# CTRL_LOGIC.net
KiCad netlist of a schematic drawn in Altium Designer
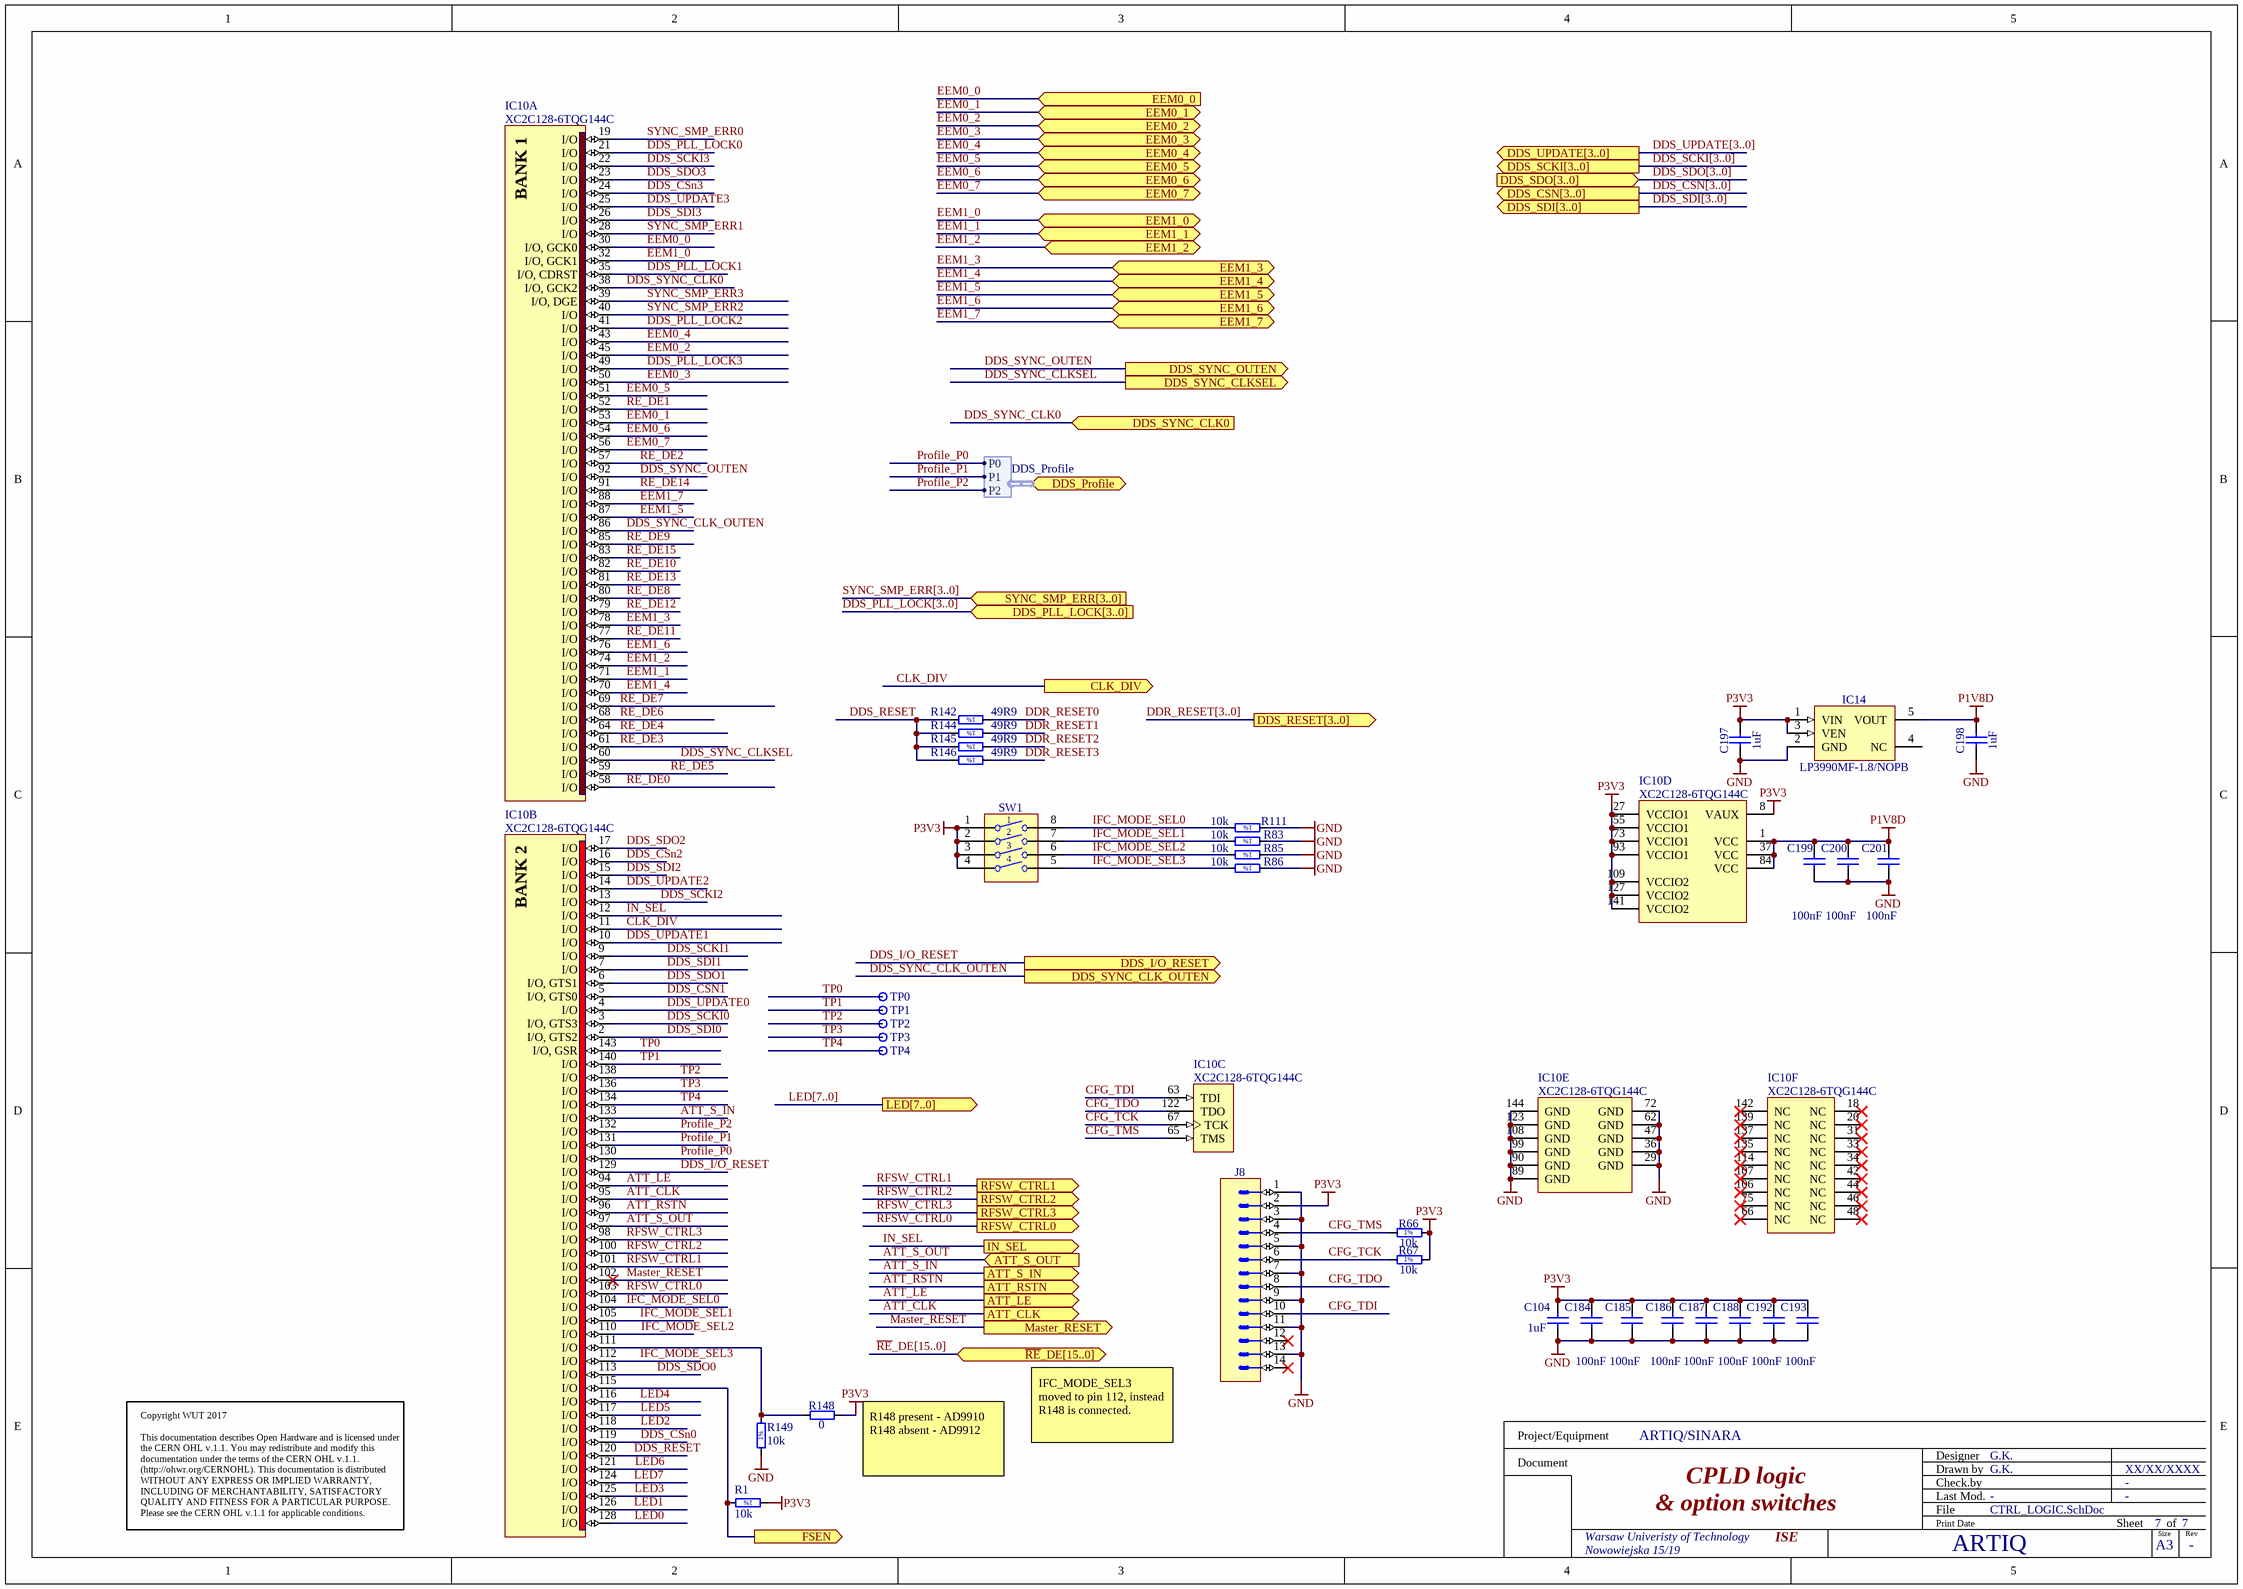
[diagram p0: CTRL_LOGIC.SchDoc]

(export (version "E")
  (design (tool "Eeschema 10.0.6"))
  (components
    (comp (ref "C104")
      (value "1uF")
      (footprint "CAPC1005X55N")
      (description "Non-polarised capacitor")
      (fields
        (field (name "PART NUMBER") "CC0402_1UF_16V_10%_X5R")
        (field (name "VOLTAGE") "16V")
        (field (name "AUTHOR") "CERN DEM JLC")
      )
      (libsource (lib "Capacitors") (part "Capacitor - non polarized"))
    )
    (comp (ref "C184")
      (value "100nF")
      (footprint "CAPC1005X55N")
      (description "Non-polarised capacitor")
      (fields
        (field (name "PART NUMBER") "CC0402_100NF_16V_10%_X5R")
        (field (name "VOLTAGE") "16V")
        (field (name "AUTHOR") "CERN DEM JLC")
      )
      (libsource (lib "Capacitors") (part "Capacitor - non polarized"))
    )
    (comp (ref "C185")
      (value "100nF")
      (footprint "CAPC1005X55N")
      (description "Non-polarised capacitor")
      (fields
        (field (name "PART NUMBER") "CC0402_100NF_16V_10%_X5R")
        (field (name "VOLTAGE") "16V")
        (field (name "AUTHOR") "CERN DEM JLC")
      )
      (libsource (lib "Capacitors") (part "Capacitor - non polarized"))
    )
    (comp (ref "C186")
      (value "100nF")
      (footprint "CAPC1005X55N")
      (description "Non-polarised capacitor")
      (fields
        (field (name "PART NUMBER") "CC0402_100NF_16V_10%_X5R")
        (field (name "VOLTAGE") "16V")
        (field (name "AUTHOR") "CERN DEM JLC")
      )
      (libsource (lib "Capacitors") (part "Capacitor - non polarized"))
    )
    (comp (ref "C187")
      (value "100nF")
      (footprint "CAPC1005X55N")
      (description "Non-polarised capacitor")
      (fields
        (field (name "PART NUMBER") "CC0402_100NF_16V_10%_X5R")
        (field (name "VOLTAGE") "16V")
        (field (name "AUTHOR") "CERN DEM JLC")
      )
      (libsource (lib "Capacitors") (part "Capacitor - non polarized"))
    )
    (comp (ref "C188")
      (value "100nF")
      (footprint "CAPC1005X55N")
      (description "Non-polarised capacitor")
      (fields
        (field (name "PART NUMBER") "CC0402_100NF_16V_10%_X5R")
        (field (name "VOLTAGE") "16V")
        (field (name "AUTHOR") "CERN DEM JLC")
      )
      (libsource (lib "Capacitors") (part "Capacitor - non polarized"))
    )
    (comp (ref "C192")
      (value "100nF")
      (footprint "CAPC1005X55N")
      (description "Non-polarised capacitor")
      (fields
        (field (name "PART NUMBER") "CC0402_100NF_16V_10%_X5R")
        (field (name "VOLTAGE") "16V")
        (field (name "AUTHOR") "CERN DEM JLC")
      )
      (libsource (lib "Capacitors") (part "Capacitor - non polarized"))
    )
    (comp (ref "C193")
      (value "100nF")
      (footprint "CAPC1005X55N")
      (description "Non-polarised capacitor")
      (fields
        (field (name "PART NUMBER") "CC0402_100NF_16V_10%_X5R")
        (field (name "VOLTAGE") "16V")
        (field (name "AUTHOR") "CERN DEM JLC")
      )
      (libsource (lib "Capacitors") (part "Capacitor - non polarized"))
    )
    (comp (ref "C197")
      (value "1uF")
      (footprint "CAPC1005X55N")
      (description "Non-polarised capacitor")
      (fields
        (field (name "PART NUMBER") "CC0402_1UF_16V_10%_X5R")
        (field (name "VOLTAGE") "16V")
        (field (name "AUTHOR") "CERN DEM JLC")
      )
      (libsource (lib "Capacitors") (part "Capacitor - non polarized"))
    )
    (comp (ref "C198")
      (value "1uF")
      (footprint "CAPC1005X55N")
      (description "Non-polarised capacitor")
      (fields
        (field (name "PART NUMBER") "CC0402_1UF_16V_10%_X5R")
        (field (name "VOLTAGE") "16V")
        (field (name "AUTHOR") "CERN DEM JLC")
      )
      (libsource (lib "Capacitors") (part "Capacitor - non polarized"))
    )
    (comp (ref "C199")
      (value "100nF")
      (footprint "CAPC1005X55N")
      (description "Non-polarised capacitor")
      (fields
        (field (name "PART NUMBER") "CC0402_100NF_16V_10%_X5R")
        (field (name "VOLTAGE") "16V")
        (field (name "AUTHOR") "CERN DEM JLC")
      )
      (libsource (lib "Capacitors") (part "Capacitor - non polarized"))
    )
    (comp (ref "C200")
      (value "100nF")
      (footprint "CAPC1005X55N")
      (description "Non-polarised capacitor")
      (fields
        (field (name "PART NUMBER") "CC0402_100NF_16V_10%_X5R")
        (field (name "VOLTAGE") "16V")
        (field (name "AUTHOR") "CERN DEM JLC")
      )
      (libsource (lib "Capacitors") (part "Capacitor - non polarized"))
    )
    (comp (ref "C201")
      (value "100nF")
      (footprint "CAPC1005X55N")
      (description "Non-polarised capacitor")
      (fields
        (field (name "PART NUMBER") "CC0402_100NF_16V_10%_X5R")
        (field (name "VOLTAGE") "16V")
        (field (name "AUTHOR") "CERN DEM JLC")
      )
      (libsource (lib "Capacitors") (part "Capacitor - non polarized"))
    )
    (comp (ref "IC10")
      (value "XC2C128-6TQG144C")
      (footprint "QFP50P2200X2200X160-144N")
      (description "CoolRunner-II 1.8V, 128 Macrocell CPLD, 100 User I/Os, 144-Pin TQFP, Commercial Grade, Pb-Free")
      (fields (field (name "MANUFACTURER") "XILINX") (field (name "AUTHOR") "CERN DEM JLC"))
      (libsource (lib "ICs And Semiconductors") (part "XC2C128-6TQG144C"))
    )
    (comp (ref "IC14")
      (value "LP3990MF-1.8/NOPB")
      (footprint "SOT95P284X122-5N")
      (description "1.8V, 150mA Linear Voltage Regulator For Digital Applications")
      (fields (field (name "MANUFACTURER") "TEXAS INSTRUMENTS") (field (name "AUTHOR") "CERN DEM JLC"))
      (libsource (lib "ICs And Semiconductors") (part "LP3990MF"))
    )
    (comp (ref "J8")
      (value "Milli-Grid™")
      (footprint "MOLEX_87832-1420")
      (description "Connector 14 Male")
      (fields
        (field (name "PART NUMBER") "MOLEX_87832-1420")
        (field (name "MANUFACTURER") "MOLEX")
        (field (name "AUTHOR") "CERN DEM JLC")
      )
      (libsource (lib "Connectors") (part "Connector 14 Male"))
    )
    (comp (ref "R1")
      (value "10k")
      (footprint "RESC1005X40N")
      (description "Resistor - 1%")
      (fields
        (field (name "PART NUMBER") "R0402_10K_1%_0.0625W_100PPM")
        (field (name "POWER") "0.0625W")
        (field (name "AUTHOR") "CERN DEM JLC")
      )
      (libsource (lib "Resistors") (part "Resistor - 1%"))
    )
    (comp (ref "R66")
      (value "10k")
      (footprint "RESC1005X40N")
      (description "Resistor - 1%")
      (fields
        (field (name "PART NUMBER") "R0402_10K_1%_0.0625W_100PPM")
        (field (name "POWER") "0.0625W")
        (field (name "AUTHOR") "CERN DEM JLC")
      )
      (libsource (lib "Resistors") (part "Resistor - 1%"))
    )
    (comp (ref "R67")
      (value "10k")
      (footprint "RESC1005X40N")
      (description "Resistor - 1%")
      (fields
        (field (name "PART NUMBER") "R0402_10K_1%_0.0625W_100PPM")
        (field (name "POWER") "0.0625W")
        (field (name "AUTHOR") "CERN DEM JLC")
      )
      (libsource (lib "Resistors") (part "Resistor - 1%"))
    )
    (comp (ref "R83")
      (value "10k")
      (footprint "RESC1005X40N")
      (description "Resistor - 1%")
      (fields
        (field (name "PART NUMBER") "R0402_10K_1%_0.0625W_100PPM")
        (field (name "POWER") "0.0625W")
        (field (name "AUTHOR") "CERN DEM JLC")
      )
      (libsource (lib "Resistors") (part "Resistor - 1%"))
    )
    (comp (ref "R85")
      (value "10k")
      (footprint "RESC1005X40N")
      (description "Resistor - 1%")
      (fields
        (field (name "PART NUMBER") "R0402_10K_1%_0.0625W_100PPM")
        (field (name "POWER") "0.0625W")
        (field (name "AUTHOR") "CERN DEM JLC")
      )
      (libsource (lib "Resistors") (part "Resistor - 1%"))
    )
    (comp (ref "R86")
      (value "10k")
      (footprint "RESC1005X40N")
      (description "Resistor - 1%")
      (fields
        (field (name "PART NUMBER") "R0402_10K_1%_0.0625W_100PPM")
        (field (name "POWER") "0.0625W")
        (field (name "AUTHOR") "CERN DEM JLC")
      )
      (libsource (lib "Resistors") (part "Resistor - 1%"))
    )
    (comp (ref "R111")
      (value "10k")
      (footprint "RESC1005X40N")
      (description "Resistor - 1%")
      (fields
        (field (name "PART NUMBER") "R0402_10K_1%_0.0625W_100PPM")
        (field (name "POWER") "0.0625W")
        (field (name "AUTHOR") "CERN DEM JLC")
      )
      (libsource (lib "Resistors") (part "Resistor - 1%"))
    )
    (comp (ref "R142")
      (value "49R9")
      (footprint "RESC1005X40N")
      (description "Resistor - 1%")
      (fields
        (field (name "PART NUMBER") "R0402_49R9_1%_0.0625W_100PPM")
        (field (name "POWER") "0.0625W")
        (field (name "AUTHOR") "CERN DEM JLC")
      )
      (libsource (lib "Resistors") (part "Resistor - 1%"))
    )
    (comp (ref "R144")
      (value "49R9")
      (footprint "RESC1005X40N")
      (description "Resistor - 1%")
      (fields
        (field (name "PART NUMBER") "R0402_49R9_1%_0.0625W_100PPM")
        (field (name "POWER") "0.0625W")
        (field (name "AUTHOR") "CERN DEM JLC")
      )
      (libsource (lib "Resistors") (part "Resistor - 1%"))
    )
    (comp (ref "R145")
      (value "49R9")
      (footprint "RESC1005X40N")
      (description "Resistor - 1%")
      (fields
        (field (name "PART NUMBER") "R0402_49R9_1%_0.0625W_100PPM")
        (field (name "POWER") "0.0625W")
        (field (name "AUTHOR") "CERN DEM JLC")
      )
      (libsource (lib "Resistors") (part "Resistor - 1%"))
    )
    (comp (ref "R146")
      (value "49R9")
      (footprint "RESC1005X40N")
      (description "Resistor - 1%")
      (fields
        (field (name "PART NUMBER") "R0402_49R9_1%_0.0625W_100PPM")
        (field (name "POWER") "0.0625W")
        (field (name "AUTHOR") "CERN DEM JLC")
      )
      (libsource (lib "Resistors") (part "Resistor - 1%"))
    )
    (comp (ref "R148")
      (value "0")
      (footprint "RESC1005X40N")
      (description "Resistor")
      (fields
        (field (name "PART NUMBER") "R0402_0R_JUMPER")
        (field (name "MANUFACTURER") "GENERIC")
        (field (name "AUTHOR") "CERN DEM JLC")
      )
      (libsource (lib "Resistors") (part "Resistor"))
    )
    (comp (ref "R149")
      (value "10k")
      (footprint "RESC1005X40N")
      (description "Resistor - 1%")
      (fields
        (field (name "PART NUMBER") "R0402_10K_1%_0.0625W_100PPM")
        (field (name "POWER") "0.0625W")
        (field (name "AUTHOR") "CERN DEM JLC")
      )
      (libsource (lib "Resistors") (part "Resistor - 1%"))
    )
    (comp (ref "SW1")
      (value "Switch")
      (footprint "SW_OMRON_A6S-4102-H")
      (description "4 Ways SPST DIP Switch")
      (fields
        (field (name "PART NUMBER") "SW_OMRON_A6S-4102-H")
        (field (name "MANUFACTURER") "OMRON")
        (field (name "AUTHOR") "CERN DEM JMW")
      )
      (libsource (lib "Eletro-mechanical") (part "SW 4x SPST DIP Switch"))
    )
    (comp (ref "TP0")
      (value "Test Point")
      (footprint "TPS127")
      (fields (field (name "PART NUMBER") "SMD_PAD_1.27X1.27MM") (field (name "AUTHOR") "CERN DEM JLC"))
      (libsource (lib "Eletro-mechanical") (part "Test Point"))
    )
    (comp (ref "TP1")
      (value "Test Point")
      (footprint "TPS127")
      (fields (field (name "PART NUMBER") "SMD_PAD_1.27X1.27MM") (field (name "AUTHOR") "CERN DEM JLC"))
      (libsource (lib "Eletro-mechanical") (part "Test Point"))
    )
    (comp (ref "TP2")
      (value "Test Point")
      (footprint "TPS127")
      (fields (field (name "PART NUMBER") "SMD_PAD_1.27X1.27MM") (field (name "AUTHOR") "CERN DEM JLC"))
      (libsource (lib "Eletro-mechanical") (part "Test Point"))
    )
    (comp (ref "TP3")
      (value "Test Point")
      (footprint "TPS127")
      (fields (field (name "PART NUMBER") "SMD_PAD_1.27X1.27MM") (field (name "AUTHOR") "CERN DEM JLC"))
      (libsource (lib "Eletro-mechanical") (part "Test Point"))
    )
    (comp (ref "TP4")
      (value "Test Point")
      (footprint "TPS127")
      (fields (field (name "PART NUMBER") "SMD_PAD_1.27X1.27MM") (field (name "AUTHOR") "CERN DEM JLC"))
      (libsource (lib "Eletro-mechanical") (part "Test Point"))
    )
  )
  (nets
    (net (code "5") (name "/ATT_CLK") (class "Default")
      (node (ref "IC10") (pin "95") (pinfunction "I/O_95") (pintype "bidirectional"))
    )
    (net (code "6") (name "/ATT_LE") (class "Default")
      (node (ref "IC10") (pin "94") (pinfunction "I/O_94") (pintype "bidirectional"))
    )
    (net (code "7") (name "/ATT_RSTN") (class "Default")
      (node (ref "IC10") (pin "96") (pinfunction "I/O_96") (pintype "bidirectional"))
    )
    (net (code "8") (name "/ATT_S_IN") (class "Default")
      (node (ref "IC10") (pin "133") (pinfunction "I/O_133") (pintype "bidirectional"))
    )
    (net (code "9") (name "/ATT_S_OUT") (class "Default")
      (node (ref "IC10") (pin "97") (pinfunction "I/O_97") (pintype "bidirectional"))
    )
    (net (code "10") (name "/CFG_TCK") (class "Default")
      (node (ref "IC10") (pin "67") (pinfunction "TCK_67") (pintype "input"))
      (node (ref "J8") (pin "6") (pinfunction "6_6") (pintype "bidirectional"))
      (node (ref "R67") (pin "1") (pinfunction "1_1") (pintype "passive"))
    )
    (net (code "11") (name "/CFG_TDI") (class "Default")
      (node (ref "IC10") (pin "63") (pinfunction "TDI_63") (pintype "input"))
      (node (ref "J8") (pin "10") (pinfunction "10_10") (pintype "bidirectional"))
    )
    (net (code "12") (name "/CFG_TDO") (class "Default")
      (node (ref "IC10") (pin "122") (pinfunction "TDO_122") (pintype "passive"))
      (node (ref "J8") (pin "8") (pinfunction "8_8") (pintype "bidirectional"))
    )
    (net (code "13") (name "/CFG_TMS") (class "Default")
      (node (ref "IC10") (pin "65") (pinfunction "TMS_65") (pintype "input"))
      (node (ref "J8") (pin "4") (pinfunction "4_4") (pintype "bidirectional"))
      (node (ref "R66") (pin "1") (pinfunction "1_1") (pintype "passive"))
    )
    (net (code "14") (name "/CLK_DIV") (class "Default")
      (node (ref "IC10") (pin "11") (pinfunction "I/O_11") (pintype "bidirectional"))
    )
    (net (code "15") (name "/DDR_RESET0") (class "Default")
      (node (ref "R142") (pin "1") (pinfunction "1_1") (pintype "passive"))
    )
    (net (code "16") (name "/DDR_RESET1") (class "Default")
      (node (ref "R144") (pin "1") (pinfunction "1_1") (pintype "passive"))
    )
    (net (code "17") (name "/DDR_RESET2") (class "Default")
      (node (ref "R145") (pin "1") (pinfunction "1_1") (pintype "passive"))
    )
    (net (code "18") (name "/DDR_RESET3") (class "Default")
      (node (ref "R146") (pin "1") (pinfunction "1_1") (pintype "passive"))
    )
    (net (code "20") (name "/DDS_CSN1") (class "Default")
      (node (ref "IC10") (pin "5") (pinfunction "I/O,_GTS0_5") (pintype "bidirectional"))
    )
    (net (code "22") (name "/DDS_CSn0") (class "Default")
      (node (ref "IC10") (pin "119") (pinfunction "I/O_119") (pintype "bidirectional"))
    )
    (net (code "23") (name "/DDS_CSn2") (class "Default")
      (node (ref "IC10") (pin "16") (pinfunction "I/O_16") (pintype "bidirectional"))
    )
    (net (code "24") (name "/DDS_CSn3") (class "Default")
      (node (ref "IC10") (pin "24") (pinfunction "I/O_24") (pintype "bidirectional"))
    )
    (net (code "25") (name "/DDS_I{slash}O_RESET") (class "Default")
      (node (ref "IC10") (pin "129") (pinfunction "I/O_129") (pintype "bidirectional"))
    )
    (net (code "26") (name "/DDS_PLL_LOCK0") (class "Default")
      (node (ref "IC10") (pin "21") (pinfunction "I/O_21") (pintype "bidirectional"))
    )
    (net (code "27") (name "/DDS_PLL_LOCK1") (class "Default")
      (node (ref "IC10") (pin "35") (pinfunction "I/O,_CDRST_35") (pintype "bidirectional"))
    )
    (net (code "28") (name "/DDS_PLL_LOCK2") (class "Default")
      (node (ref "IC10") (pin "41") (pinfunction "I/O_41") (pintype "bidirectional"))
    )
    (net (code "29") (name "/DDS_PLL_LOCK3") (class "Default")
      (node (ref "IC10") (pin "49") (pinfunction "I/O_49") (pintype "bidirectional"))
    )
    (net (code "31") (name "/DDS_RESET") (class "Default")
      (node (ref "IC10") (pin "120") (pinfunction "I/O_120") (pintype "bidirectional"))
      (node (ref "R142") (pin "2") (pinfunction "2_2") (pintype "passive"))
      (node (ref "R144") (pin "2") (pinfunction "2_2") (pintype "passive"))
      (node (ref "R145") (pin "2") (pinfunction "2_2") (pintype "passive"))
      (node (ref "R146") (pin "2") (pinfunction "2_2") (pintype "passive"))
    )
    (net (code "32") (name "/DDS_SCKI0") (class "Default")
      (node (ref "IC10") (pin "3") (pinfunction "I/O,_GTS3_3") (pintype "bidirectional"))
    )
    (net (code "33") (name "/DDS_SCKI1") (class "Default")
      (node (ref "IC10") (pin "9") (pinfunction "I/O_9") (pintype "bidirectional"))
    )
    (net (code "34") (name "/DDS_SCKI2") (class "Default")
      (node (ref "IC10") (pin "13") (pinfunction "I/O_13") (pintype "bidirectional"))
    )
    (net (code "35") (name "/DDS_SCKI3") (class "Default")
      (node (ref "IC10") (pin "22") (pinfunction "I/O_22") (pintype "bidirectional"))
    )
    (net (code "37") (name "/DDS_SDI0") (class "Default")
      (node (ref "IC10") (pin "2") (pinfunction "I/O,_GTS2_2") (pintype "bidirectional"))
    )
    (net (code "38") (name "/DDS_SDI1") (class "Default")
      (node (ref "IC10") (pin "7") (pinfunction "I/O_7") (pintype "bidirectional"))
    )
    (net (code "39") (name "/DDS_SDI2") (class "Default")
      (node (ref "IC10") (pin "15") (pinfunction "I/O_15") (pintype "bidirectional"))
    )
    (net (code "40") (name "/DDS_SDI3") (class "Default")
      (node (ref "IC10") (pin "26") (pinfunction "I/O_26") (pintype "bidirectional"))
    )
    (net (code "42") (name "/DDS_SDO0") (class "Default")
      (node (ref "IC10") (pin "113") (pinfunction "I/O_113") (pintype "bidirectional"))
    )
    (net (code "43") (name "/DDS_SDO1") (class "Default")
      (node (ref "IC10") (pin "6") (pinfunction "I/O,_GTS1_6") (pintype "bidirectional"))
    )
    (net (code "44") (name "/DDS_SDO2") (class "Default")
      (node (ref "IC10") (pin "17") (pinfunction "I/O_17") (pintype "bidirectional"))
    )
    (net (code "45") (name "/DDS_SDO3") (class "Default")
      (node (ref "IC10") (pin "23") (pinfunction "I/O_23") (pintype "bidirectional"))
    )
    (net (code "47") (name "/DDS_SYNC_CLK0") (class "Default")
      (node (ref "IC10") (pin "38") (pinfunction "I/O,_GCK2_38") (pintype "bidirectional"))
    )
    (net (code "48") (name "/DDS_SYNC_CLKSEL") (class "Default")
      (node (ref "IC10") (pin "60") (pinfunction "I/O_60") (pintype "bidirectional"))
    )
    (net (code "49") (name "/DDS_SYNC_CLK_OUTEN") (class "Default")
      (node (ref "IC10") (pin "86") (pinfunction "I/O_86") (pintype "bidirectional"))
    )
    (net (code "50") (name "/DDS_SYNC_OUTEN") (class "Default")
      (node (ref "IC10") (pin "92") (pinfunction "I/O_92") (pintype "bidirectional"))
    )
    (net (code "51") (name "/DDS_UPDATE0") (class "Default")
      (node (ref "IC10") (pin "4") (pinfunction "I/O_4") (pintype "bidirectional"))
    )
    (net (code "52") (name "/DDS_UPDATE1") (class "Default")
      (node (ref "IC10") (pin "10") (pinfunction "I/O_10") (pintype "bidirectional"))
    )
    (net (code "53") (name "/DDS_UPDATE2") (class "Default")
      (node (ref "IC10") (pin "14") (pinfunction "I/O_14") (pintype "bidirectional"))
    )
    (net (code "54") (name "/DDS_UPDATE3") (class "Default")
      (node (ref "IC10") (pin "25") (pinfunction "I/O_25") (pintype "bidirectional"))
    )
    (net (code "56") (name "/EEM0_0") (class "Default")
      (node (ref "IC10") (pin "30") (pinfunction "I/O,_GCK0_30") (pintype "bidirectional"))
    )
    (net (code "57") (name "/EEM0_1") (class "Default")
      (node (ref "IC10") (pin "53") (pinfunction "I/O_53") (pintype "bidirectional"))
    )
    (net (code "58") (name "/EEM0_2") (class "Default")
      (node (ref "IC10") (pin "45") (pinfunction "I/O_45") (pintype "bidirectional"))
    )
    (net (code "59") (name "/EEM0_3") (class "Default")
      (node (ref "IC10") (pin "50") (pinfunction "I/O_50") (pintype "bidirectional"))
    )
    (net (code "60") (name "/EEM0_4") (class "Default")
      (node (ref "IC10") (pin "43") (pinfunction "I/O_43") (pintype "bidirectional"))
    )
    (net (code "61") (name "/EEM0_5") (class "Default")
      (node (ref "IC10") (pin "51") (pinfunction "I/O_51") (pintype "bidirectional"))
    )
    (net (code "62") (name "/EEM0_6") (class "Default")
      (node (ref "IC10") (pin "54") (pinfunction "I/O_54") (pintype "bidirectional"))
    )
    (net (code "63") (name "/EEM0_7") (class "Default")
      (node (ref "IC10") (pin "56") (pinfunction "I/O_56") (pintype "bidirectional"))
    )
    (net (code "64") (name "/EEM1_0") (class "Default")
      (node (ref "IC10") (pin "32") (pinfunction "I/O,_GCK1_32") (pintype "bidirectional"))
    )
    (net (code "65") (name "/EEM1_1") (class "Default")
      (node (ref "IC10") (pin "71") (pinfunction "I/O_71") (pintype "bidirectional"))
    )
    (net (code "66") (name "/EEM1_2") (class "Default")
      (node (ref "IC10") (pin "74") (pinfunction "I/O_74") (pintype "bidirectional"))
    )
    (net (code "67") (name "/EEM1_3") (class "Default")
      (node (ref "IC10") (pin "78") (pinfunction "I/O_78") (pintype "bidirectional"))
    )
    (net (code "68") (name "/EEM1_4") (class "Default")
      (node (ref "IC10") (pin "70") (pinfunction "I/O_70") (pintype "bidirectional"))
    )
    (net (code "69") (name "/EEM1_5") (class "Default")
      (node (ref "IC10") (pin "87") (pinfunction "I/O_87") (pintype "bidirectional"))
    )
    (net (code "70") (name "/EEM1_6") (class "Default")
      (node (ref "IC10") (pin "76") (pinfunction "I/O_76") (pintype "bidirectional"))
    )
    (net (code "71") (name "/EEM1_7") (class "Default")
      (node (ref "IC10") (pin "88") (pinfunction "I/O_88") (pintype "bidirectional"))
    )
    (net (code "72") (name "/FSEN") (class "Default")
      (node (ref "IC10") (pin "115") (pinfunction "I/O_115") (pintype "bidirectional"))
      (node (ref "R1") (pin "2") (pinfunction "2_2") (pintype "passive"))
    )
    (net (code "73") (name "/IFC_MODE_SEL0") (class "Default")
      (node (ref "IC10") (pin "104") (pinfunction "I/O_104") (pintype "bidirectional"))
      (node (ref "R111") (pin "2") (pinfunction "2_2") (pintype "passive"))
      (node (ref "SW1") (pin "8") (pinfunction "8_8") (pintype "passive"))
    )
    (net (code "74") (name "/IFC_MODE_SEL1") (class "Default")
      (node (ref "IC10") (pin "105") (pinfunction "I/O_105") (pintype "bidirectional"))
      (node (ref "R83") (pin "2") (pinfunction "2_2") (pintype "passive"))
      (node (ref "SW1") (pin "7") (pinfunction "7_7") (pintype "passive"))
    )
    (net (code "75") (name "/IFC_MODE_SEL2") (class "Default")
      (node (ref "IC10") (pin "110") (pinfunction "I/O_110") (pintype "bidirectional"))
      (node (ref "R85") (pin "2") (pinfunction "2_2") (pintype "passive"))
      (node (ref "SW1") (pin "6") (pinfunction "6_6") (pintype "passive"))
    )
    (net (code "76") (name "/IFC_MODE_SEL3") (class "Default")
      (node (ref "IC10") (pin "112") (pinfunction "I/O_112") (pintype "bidirectional"))
      (node (ref "R86") (pin "2") (pinfunction "2_2") (pintype "passive"))
      (node (ref "SW1") (pin "5") (pinfunction "5_5") (pintype "passive"))
    )
    (net (code "77") (name "/IN_SEL") (class "Default")
      (node (ref "IC10") (pin "12") (pinfunction "I/O_12") (pintype "bidirectional"))
    )
    (net (code "78") (name "/LED0") (class "Default")
      (node (ref "IC10") (pin "128") (pinfunction "I/O_128") (pintype "bidirectional"))
    )
    (net (code "79") (name "/LED1") (class "Default")
      (node (ref "IC10") (pin "126") (pinfunction "I/O_126") (pintype "bidirectional"))
    )
    (net (code "80") (name "/LED2") (class "Default")
      (node (ref "IC10") (pin "118") (pinfunction "I/O_118") (pintype "bidirectional"))
    )
    (net (code "81") (name "/LED3") (class "Default")
      (node (ref "IC10") (pin "125") (pinfunction "I/O_125") (pintype "bidirectional"))
    )
    (net (code "82") (name "/LED4") (class "Default")
      (node (ref "IC10") (pin "116") (pinfunction "I/O_116") (pintype "bidirectional"))
    )
    (net (code "83") (name "/LED5") (class "Default")
      (node (ref "IC10") (pin "117") (pinfunction "I/O_117") (pintype "bidirectional"))
    )
    (net (code "84") (name "/LED6") (class "Default")
      (node (ref "IC10") (pin "121") (pinfunction "I/O_121") (pintype "bidirectional"))
    )
    (net (code "85") (name "/LED7") (class "Default")
      (node (ref "IC10") (pin "124") (pinfunction "I/O_124") (pintype "bidirectional"))
    )
    (net (code "87") (name "/Master_RESET") (class "Default")
      (node (ref "IC10") (pin "102") (pinfunction "I/O_102") (pintype "bidirectional"))
    )
    (net (code "88") (name "/Profile_P0") (class "Default")
      (node (ref "IC10") (pin "130") (pinfunction "I/O_130") (pintype "bidirectional"))
    )
    (net (code "89") (name "/Profile_P1") (class "Default")
      (node (ref "IC10") (pin "131") (pinfunction "I/O_131") (pintype "bidirectional"))
    )
    (net (code "90") (name "/Profile_P2") (class "Default")
      (node (ref "IC10") (pin "132") (pinfunction "I/O_132") (pintype "bidirectional"))
    )
    (net (code "91") (name "/RFSW_CTRL0") (class "Default")
      (node (ref "IC10") (pin "103") (pinfunction "I/O_103") (pintype "bidirectional"))
    )
    (net (code "92") (name "/RFSW_CTRL1") (class "Default")
      (node (ref "IC10") (pin "101") (pinfunction "I/O_101") (pintype "bidirectional"))
    )
    (net (code "93") (name "/RFSW_CTRL2") (class "Default")
      (node (ref "IC10") (pin "100") (pinfunction "I/O_100") (pintype "bidirectional"))
    )
    (net (code "94") (name "/RFSW_CTRL3") (class "Default")
      (node (ref "IC10") (pin "98") (pinfunction "I/O_98") (pintype "bidirectional"))
    )
    (net (code "95") (name "/SYNC_SMP_ERR0") (class "Default")
      (node (ref "IC10") (pin "19") (pinfunction "I/O_19") (pintype "bidirectional"))
    )
    (net (code "96") (name "/SYNC_SMP_ERR1") (class "Default")
      (node (ref "IC10") (pin "28") (pinfunction "I/O_28") (pintype "bidirectional"))
    )
    (net (code "97") (name "/SYNC_SMP_ERR2") (class "Default")
      (node (ref "IC10") (pin "40") (pinfunction "I/O_40") (pintype "bidirectional"))
    )
    (net (code "98") (name "/SYNC_SMP_ERR3") (class "Default")
      (node (ref "IC10") (pin "39") (pinfunction "I/O,_DGE_39") (pintype "bidirectional"))
    )
    (net (code "100") (name "/TP0") (class "Default")
      (node (ref "IC10") (pin "143") (pinfunction "I/O,_GSR_143") (pintype "bidirectional"))
      (node (ref "TP0") (pin "1") (pinfunction "1_1") (pintype "bidirectional"))
    )
    (net (code "101") (name "/TP1") (class "Default")
      (node (ref "IC10") (pin "140") (pinfunction "I/O_140") (pintype "bidirectional"))
      (node (ref "TP1") (pin "1") (pinfunction "1_1") (pintype "bidirectional"))
    )
    (net (code "102") (name "/TP2") (class "Default")
      (node (ref "IC10") (pin "138") (pinfunction "I/O_138") (pintype "bidirectional"))
      (node (ref "TP2") (pin "1") (pinfunction "1_1") (pintype "bidirectional"))
    )
    (net (code "103") (name "/TP3") (class "Default")
      (node (ref "IC10") (pin "136") (pinfunction "I/O_136") (pintype "bidirectional"))
      (node (ref "TP3") (pin "1") (pinfunction "1_1") (pintype "bidirectional"))
    )
    (net (code "104") (name "/TP4") (class "Default")
      (node (ref "IC10") (pin "134") (pinfunction "I/O_134") (pintype "bidirectional"))
      (node (ref "TP4") (pin "1") (pinfunction "1_1") (pintype "bidirectional"))
    )
    (net (code "106") (name "/~{RE}_DE0") (class "Default")
      (node (ref "IC10") (pin "58") (pinfunction "I/O_58") (pintype "bidirectional"))
    )
    (net (code "107") (name "/~{RE}_DE1") (class "Default")
      (node (ref "IC10") (pin "52") (pinfunction "I/O_52") (pintype "bidirectional"))
    )
    (net (code "108") (name "/~{RE}_DE2") (class "Default")
      (node (ref "IC10") (pin "57") (pinfunction "I/O_57") (pintype "bidirectional"))
    )
    (net (code "109") (name "/~{RE}_DE3") (class "Default")
      (node (ref "IC10") (pin "61") (pinfunction "I/O_61") (pintype "bidirectional"))
    )
    (net (code "110") (name "/~{RE}_DE4") (class "Default")
      (node (ref "IC10") (pin "64") (pinfunction "I/O_64") (pintype "bidirectional"))
    )
    (net (code "111") (name "/~{RE}_DE5") (class "Default")
      (node (ref "IC10") (pin "59") (pinfunction "I/O_59") (pintype "bidirectional"))
    )
    (net (code "112") (name "/~{RE}_DE6") (class "Default")
      (node (ref "IC10") (pin "68") (pinfunction "I/O_68") (pintype "bidirectional"))
    )
    (net (code "113") (name "/~{RE}_DE7") (class "Default")
      (node (ref "IC10") (pin "69") (pinfunction "I/O_69") (pintype "bidirectional"))
    )
    (net (code "114") (name "/~{RE}_DE8") (class "Default")
      (node (ref "IC10") (pin "80") (pinfunction "I/O_80") (pintype "bidirectional"))
    )
    (net (code "115") (name "/~{RE}_DE9") (class "Default")
      (node (ref "IC10") (pin "85") (pinfunction "I/O_85") (pintype "bidirectional"))
    )
    (net (code "116") (name "/~{RE}_DE10") (class "Default")
      (node (ref "IC10") (pin "82") (pinfunction "I/O_82") (pintype "bidirectional"))
    )
    (net (code "117") (name "/~{RE}_DE11") (class "Default")
      (node (ref "IC10") (pin "77") (pinfunction "I/O_77") (pintype "bidirectional"))
    )
    (net (code "118") (name "/~{RE}_DE12") (class "Default")
      (node (ref "IC10") (pin "79") (pinfunction "I/O_79") (pintype "bidirectional"))
    )
    (net (code "119") (name "/~{RE}_DE13") (class "Default")
      (node (ref "IC10") (pin "81") (pinfunction "I/O_81") (pintype "bidirectional"))
    )
    (net (code "120") (name "/~{RE}_DE14") (class "Default")
      (node (ref "IC10") (pin "91") (pinfunction "I/O_91") (pintype "bidirectional"))
    )
    (net (code "121") (name "/~{RE}_DE15") (class "Default")
      (node (ref "IC10") (pin "83") (pinfunction "I/O_83") (pintype "bidirectional"))
    )
    (net (code "123") (name "GND") (class "Default")
      (node (ref "C104") (pin "1") (pinfunction "1_1") (pintype "passive"))
      (node (ref "C184") (pin "1") (pinfunction "1_1") (pintype "passive"))
      (node (ref "C185") (pin "1") (pinfunction "1_1") (pintype "passive"))
      (node (ref "C186") (pin "1") (pinfunction "1_1") (pintype "passive"))
      (node (ref "C187") (pin "1") (pinfunction "1_1") (pintype "passive"))
      (node (ref "C188") (pin "1") (pinfunction "1_1") (pintype "passive"))
      (node (ref "C192") (pin "1") (pinfunction "1_1") (pintype "passive"))
      (node (ref "C193") (pin "1") (pinfunction "1_1") (pintype "passive"))
      (node (ref "C197") (pin "1") (pinfunction "1_1") (pintype "passive"))
      (node (ref "C198") (pin "1") (pinfunction "1_1") (pintype "passive"))
      (node (ref "C199") (pin "1") (pinfunction "1_1") (pintype "passive"))
      (node (ref "C200") (pin "1") (pinfunction "1_1") (pintype "passive"))
      (node (ref "C201") (pin "1") (pinfunction "1_1") (pintype "passive"))
      (node (ref "IC10") (pin "108") (pinfunction "GND_108") (pintype "power_in"))
      (node (ref "IC10") (pin "123") (pinfunction "GND_123") (pintype "power_in"))
      (node (ref "IC10") (pin "144") (pinfunction "GND_144") (pintype "power_in"))
      (node (ref "IC10") (pin "29") (pinfunction "GND_29") (pintype "power_in"))
      (node (ref "IC10") (pin "36") (pinfunction "GND_36") (pintype "power_in"))
      (node (ref "IC10") (pin "47") (pinfunction "GND_47") (pintype "power_in"))
      (node (ref "IC10") (pin "62") (pinfunction "GND_62") (pintype "power_in"))
      (node (ref "IC10") (pin "72") (pinfunction "GND_72") (pintype "power_in"))
      (node (ref "IC10") (pin "89") (pinfunction "GND_89") (pintype "power_in"))
      (node (ref "IC10") (pin "90") (pinfunction "GND_90") (pintype "power_in"))
      (node (ref "IC10") (pin "99") (pinfunction "GND_99") (pintype "power_in"))
      (node (ref "IC14") (pin "2") (pinfunction "GND_2") (pintype "power_in"))
      (node (ref "J8") (pin "1") (pinfunction "1_1") (pintype "bidirectional"))
      (node (ref "J8") (pin "11") (pinfunction "11_11") (pintype "bidirectional"))
      (node (ref "J8") (pin "13") (pinfunction "13_13") (pintype "bidirectional"))
      (node (ref "J8") (pin "3") (pinfunction "3_3") (pintype "bidirectional"))
      (node (ref "J8") (pin "5") (pinfunction "5_5") (pintype "bidirectional"))
      (node (ref "J8") (pin "7") (pinfunction "7_7") (pintype "bidirectional"))
      (node (ref "J8") (pin "9") (pinfunction "9_9") (pintype "bidirectional"))
      (node (ref "R111") (pin "1") (pinfunction "1_1") (pintype "passive"))
      (node (ref "R149") (pin "1") (pinfunction "1_1") (pintype "passive"))
      (node (ref "R83") (pin "1") (pinfunction "1_1") (pintype "passive"))
      (node (ref "R85") (pin "1") (pinfunction "1_1") (pintype "passive"))
      (node (ref "R86") (pin "1") (pinfunction "1_1") (pintype "passive"))
    )
    (net (code "124") (name "Net-(IC10B-I{slash}O-Pad111)") (class "Default")
      (node (ref "IC10") (pin "111") (pinfunction "I/O_111") (pintype "bidirectional"))
      (node (ref "R148") (pin "1") (pinfunction "1_1") (pintype "passive"))
      (node (ref "R149") (pin "2") (pinfunction "2_2") (pintype "passive"))
    )
    (net (code "125") (name "P1V8D") (class "Default")
      (node (ref "C198") (pin "2") (pinfunction "2_2") (pintype "passive"))
      (node (ref "C199") (pin "2") (pinfunction "2_2") (pintype "passive"))
      (node (ref "C200") (pin "2") (pinfunction "2_2") (pintype "passive"))
      (node (ref "C201") (pin "2") (pinfunction "2_2") (pintype "passive"))
      (node (ref "IC10") (pin "1") (pinfunction "VCC_1") (pintype "power_in"))
      (node (ref "IC10") (pin "37") (pinfunction "VCC_37") (pintype "power_in"))
      (node (ref "IC10") (pin "84") (pinfunction "VCC_84") (pintype "power_in"))
      (node (ref "IC14") (pin "5") (pinfunction "VOUT_5") (pintype "power_in"))
    )
    (net (code "126") (name "P3V3") (class "Default")
      (node (ref "C104") (pin "2") (pinfunction "2_2") (pintype "passive"))
      (node (ref "C184") (pin "2") (pinfunction "2_2") (pintype "passive"))
      (node (ref "C185") (pin "2") (pinfunction "2_2") (pintype "passive"))
      (node (ref "C186") (pin "2") (pinfunction "2_2") (pintype "passive"))
      (node (ref "C187") (pin "2") (pinfunction "2_2") (pintype "passive"))
      (node (ref "C188") (pin "2") (pinfunction "2_2") (pintype "passive"))
      (node (ref "C192") (pin "2") (pinfunction "2_2") (pintype "passive"))
      (node (ref "C193") (pin "2") (pinfunction "2_2") (pintype "passive"))
      (node (ref "C197") (pin "2") (pinfunction "2_2") (pintype "passive"))
      (node (ref "IC10") (pin "109") (pinfunction "VCCIO2_109") (pintype "power_in"))
      (node (ref "IC10") (pin "127") (pinfunction "VCCIO2_127") (pintype "power_in"))
      (node (ref "IC10") (pin "141") (pinfunction "VCCIO2_141") (pintype "power_in"))
      (node (ref "IC10") (pin "27") (pinfunction "VCCIO1_27") (pintype "power_in"))
      (node (ref "IC10") (pin "55") (pinfunction "VCCIO1_55") (pintype "power_in"))
      (node (ref "IC10") (pin "73") (pinfunction "VCCIO1_73") (pintype "power_in"))
      (node (ref "IC10") (pin "8") (pinfunction "VAUX_8") (pintype "power_in"))
      (node (ref "IC10") (pin "93") (pinfunction "VCCIO1_93") (pintype "power_in"))
      (node (ref "IC14") (pin "1") (pinfunction "VIN_1") (pintype "input"))
      (node (ref "IC14") (pin "3") (pinfunction "VEN_3") (pintype "input"))
      (node (ref "J8") (pin "2") (pinfunction "2_2") (pintype "bidirectional"))
      (node (ref "R1") (pin "1") (pinfunction "1_1") (pintype "passive"))
      (node (ref "R148") (pin "2") (pinfunction "2_2") (pintype "passive"))
      (node (ref "R66") (pin "2") (pinfunction "2_2") (pintype "passive"))
      (node (ref "R67") (pin "2") (pinfunction "2_2") (pintype "passive"))
      (node (ref "SW1") (pin "1") (pinfunction "1_1") (pintype "passive"))
      (node (ref "SW1") (pin "2") (pinfunction "2_2") (pintype "passive"))
      (node (ref "SW1") (pin "3") (pinfunction "3_3") (pintype "passive"))
      (node (ref "SW1") (pin "4") (pinfunction "4_4") (pintype "passive"))
    )
    (net (code "127") (name "unconnected-(IC10F-NC-Pad18)") (class "Default")
      (node (ref "IC10") (pin "18") (pinfunction "NC_18") (pintype "passive+no_connect"))
    )
    (net (code "128") (name "unconnected-(IC10F-NC-Pad20)") (class "Default")
      (node (ref "IC10") (pin "20") (pinfunction "NC_20") (pintype "passive+no_connect"))
    )
    (net (code "129") (name "unconnected-(IC10F-NC-Pad31)") (class "Default")
      (node (ref "IC10") (pin "31") (pinfunction "NC_31") (pintype "passive+no_connect"))
    )
    (net (code "130") (name "unconnected-(IC10F-NC-Pad33)") (class "Default")
      (node (ref "IC10") (pin "33") (pinfunction "NC_33") (pintype "passive+no_connect"))
    )
    (net (code "131") (name "unconnected-(IC10F-NC-Pad34)") (class "Default")
      (node (ref "IC10") (pin "34") (pinfunction "NC_34") (pintype "passive+no_connect"))
    )
    (net (code "132") (name "unconnected-(IC10F-NC-Pad42)") (class "Default")
      (node (ref "IC10") (pin "42") (pinfunction "NC_42") (pintype "passive+no_connect"))
    )
    (net (code "133") (name "unconnected-(IC10F-NC-Pad44)") (class "Default")
      (node (ref "IC10") (pin "44") (pinfunction "NC_44") (pintype "passive+no_connect"))
    )
    (net (code "134") (name "unconnected-(IC10F-NC-Pad46)") (class "Default")
      (node (ref "IC10") (pin "46") (pinfunction "NC_46") (pintype "passive+no_connect"))
    )
    (net (code "135") (name "unconnected-(IC10F-NC-Pad48)") (class "Default")
      (node (ref "IC10") (pin "48") (pinfunction "NC_48") (pintype "passive+no_connect"))
    )
    (net (code "136") (name "unconnected-(IC10F-NC-Pad66)") (class "Default")
      (node (ref "IC10") (pin "66") (pinfunction "NC_66") (pintype "passive+no_connect"))
    )
    (net (code "137") (name "unconnected-(IC10F-NC-Pad75)") (class "Default")
      (node (ref "IC10") (pin "75") (pinfunction "NC_75") (pintype "passive+no_connect"))
    )
    (net (code "138") (name "unconnected-(IC10F-NC-Pad106)") (class "Default")
      (node (ref "IC10") (pin "106") (pinfunction "NC_106") (pintype "passive+no_connect"))
    )
    (net (code "139") (name "unconnected-(IC10F-NC-Pad107)") (class "Default")
      (node (ref "IC10") (pin "107") (pinfunction "NC_107") (pintype "passive+no_connect"))
    )
    (net (code "140") (name "unconnected-(IC10F-NC-Pad114)") (class "Default")
      (node (ref "IC10") (pin "114") (pinfunction "NC_114") (pintype "passive+no_connect"))
    )
    (net (code "141") (name "unconnected-(IC10F-NC-Pad135)") (class "Default")
      (node (ref "IC10") (pin "135") (pinfunction "NC_135") (pintype "passive+no_connect"))
    )
    (net (code "142") (name "unconnected-(IC10F-NC-Pad137)") (class "Default")
      (node (ref "IC10") (pin "137") (pinfunction "NC_137") (pintype "passive+no_connect"))
    )
    (net (code "143") (name "unconnected-(IC10F-NC-Pad139)") (class "Default")
      (node (ref "IC10") (pin "139") (pinfunction "NC_139") (pintype "passive+no_connect"))
    )
    (net (code "144") (name "unconnected-(IC10F-NC-Pad142)") (class "Default")
      (node (ref "IC10") (pin "142") (pinfunction "NC_142") (pintype "passive+no_connect"))
    )
    (net (code "145") (name "unconnected-(IC14-NC-Pad4)") (class "Default")
      (node (ref "IC14") (pin "4") (pinfunction "NC_4") (pintype "passive"))
    )
    (net (code "146") (name "unconnected-(J8-Pad12)") (class "Default")
      (node (ref "J8") (pin "12") (pinfunction "12_12") (pintype "bidirectional+no_connect"))
    )
    (net (code "147") (name "unconnected-(J8-Pad14)") (class "Default")
      (node (ref "J8") (pin "14") (pinfunction "14_14") (pintype "bidirectional+no_connect"))
    )
  )
)
